# Temperatura.net
KiCad netlist of a schematic drawn in Altium Designer
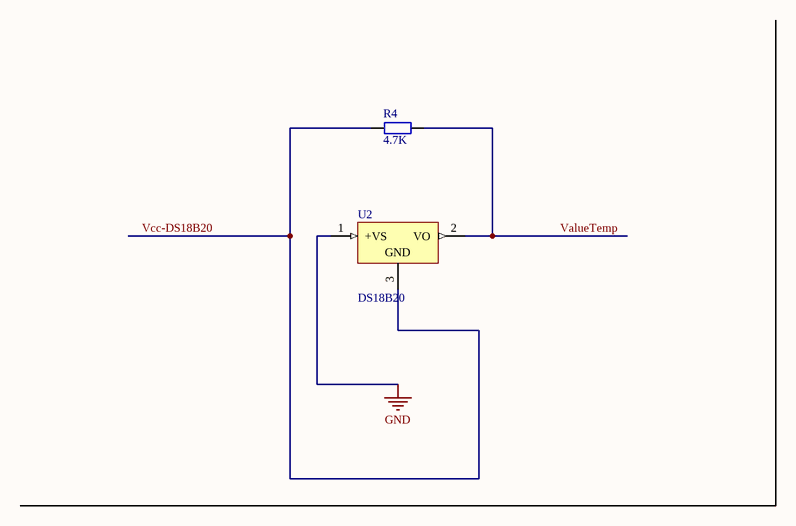
[diagram p0: Temperatura.SchDoc]

(export (version "E")
  (design (tool "Eeschema 10.0.6"))
  (components
    (comp (ref "R4")
      (value "4.7K")
      (footprint "R1206-0.55")
      (description "Resistor, generic")
      (fields (field (name "Comment") "R"))
      (libsource (lib "IFS_Altium") (part "R"))
    )
    (comp (ref "U2")
      (value "DS18B20")
      (footprint "Z03A")
      (description "Precision Centigrade Temperature Sensor, 3-pin TO-92, Pb-Free")
      (fields
        (field (name "PARTNUMBER") "LM35CAZ/NOPB")
        (field (name "MANUFACTURER") "National Semiconductor")
        (field (name "PUBLISHER") "Altium Limited")
      )
      (libsource (lib "NSC Temperature Sensor") (part "LM35CAZ/NOPB"))
    )
  )
  (nets
    (net (code "1") (name "/ValueTemp") (class "Default")
      (node (ref "R4") (pin "1") (pinfunction "1_1") (pintype "passive"))
      (node (ref "U2") (pin "2") (pinfunction "VO_2") (pintype "output"))
    )
    (net (code "2") (name "/Vcc-DS18B20") (class "Default")
      (node (ref "R4") (pin "2") (pinfunction "2_2") (pintype "passive"))
      (node (ref "U2") (pin "3") (pinfunction "GND_3") (pintype "power_in"))
    )
    (net (code "3") (name "GND") (class "Default")
      (node (ref "U2") (pin "1") (pinfunction "+VS_1") (pintype "input"))
    )
  )
)
